# QSTL_MicroDSUB_FFC.net
KiCad netlist of a schematic drawn in Altium Designer
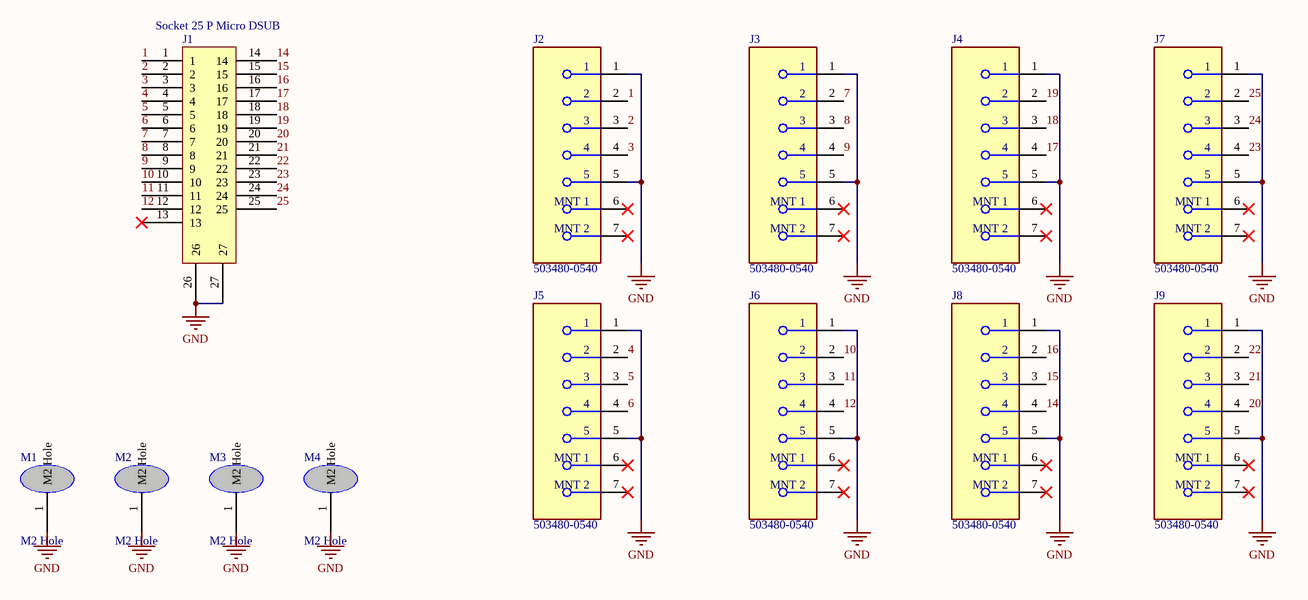
[diagram p0: QSTL_MicroDSUB_FFC.SchDoc]

(export (version "E")
  (design (tool "Eeschema 10.0.6"))
  (components
    (comp (ref "J1")
      (value "Socket 25 P Micro DSUB")
      (footprint "581-M25-213L461")
      (libsource (lib "QSTL_MicroDSUB_FFC") (part "581-M25-213L461"))
    )
    (comp (ref "J2")
      (value "503480-0540")
      (footprint "FP-503480-0540-MFG")
      (description "503480-0540 Connector FFC/FPC SKT 5 Position 0.5mm Solder Right Angle Surface Mount T/R")
      (libsource (lib "Altium Content Vault") (part "6b037d2877ced340e1c65ac82253790"))
    )
    (comp (ref "J3")
      (value "503480-0540")
      (footprint "FP-503480-0540-MFG")
      (description "503480-0540 Connector FFC/FPC SKT 5 Position 0.5mm Solder Right Angle Surface Mount T/R")
      (libsource (lib "Altium Content Vault") (part "6b037d2877ced340e1c65ac82253790"))
    )
    (comp (ref "J4")
      (value "503480-0540")
      (footprint "FP-503480-0540-MFG")
      (description "503480-0540 Connector FFC/FPC SKT 5 Position 0.5mm Solder Right Angle Surface Mount T/R")
      (libsource (lib "Altium Content Vault") (part "6b037d2877ced340e1c65ac82253790"))
    )
    (comp (ref "J5")
      (value "503480-0540")
      (footprint "FP-503480-0540-MFG")
      (description "503480-0540 Connector FFC/FPC SKT 5 Position 0.5mm Solder Right Angle Surface Mount T/R")
      (libsource (lib "Altium Content Vault") (part "6b037d2877ced340e1c65ac82253790"))
    )
    (comp (ref "J6")
      (value "503480-0540")
      (footprint "FP-503480-0540-MFG")
      (description "503480-0540 Connector FFC/FPC SKT 5 Position 0.5mm Solder Right Angle Surface Mount T/R")
      (libsource (lib "Altium Content Vault") (part "6b037d2877ced340e1c65ac82253790"))
    )
    (comp (ref "J7")
      (value "503480-0540")
      (footprint "FP-503480-0540-MFG")
      (description "503480-0540 Connector FFC/FPC SKT 5 Position 0.5mm Solder Right Angle Surface Mount T/R")
      (libsource (lib "Altium Content Vault") (part "6b037d2877ced340e1c65ac82253790"))
    )
    (comp (ref "J8")
      (value "503480-0540")
      (footprint "FP-503480-0540-MFG")
      (description "503480-0540 Connector FFC/FPC SKT 5 Position 0.5mm Solder Right Angle Surface Mount T/R")
      (libsource (lib "Altium Content Vault") (part "6b037d2877ced340e1c65ac82253790"))
    )
    (comp (ref "J9")
      (value "503480-0540")
      (footprint "FP-503480-0540-MFG")
      (description "503480-0540 Connector FFC/FPC SKT 5 Position 0.5mm Solder Right Angle Surface Mount T/R")
      (libsource (lib "Altium Content Vault") (part "6b037d2877ced340e1c65ac82253790"))
    )
    (comp (ref "M1")
      (value "M2 Hole")
      (footprint "M2_Hole")
      (libsource (lib "QSTL_MicroDSUB_FFC") (part "M2_HOLE"))
    )
    (comp (ref "M2")
      (value "M2 Hole")
      (footprint "M2_Hole")
      (libsource (lib "QSTL_MicroDSUB_FFC") (part "M2_HOLE"))
    )
    (comp (ref "M3")
      (value "M2 Hole")
      (footprint "M2_Hole")
      (libsource (lib "QSTL_MicroDSUB_FFC") (part "M2_HOLE"))
    )
    (comp (ref "M4")
      (value "M2 Hole")
      (footprint "M2_Hole")
      (libsource (lib "QSTL_MicroDSUB_FFC") (part "M2_HOLE"))
    )
  )
  (nets
    (net (code "1") (name "/1") (class "Default")
      (node (ref "J1") (pin "1") (pinfunction "1_1") (pintype "passive"))
      (node (ref "J2") (pin "2") (pinfunction "2_2") (pintype "passive"))
    )
    (net (code "2") (name "/2") (class "Default")
      (node (ref "J1") (pin "2") (pinfunction "2_2") (pintype "passive"))
      (node (ref "J2") (pin "3") (pinfunction "3_3") (pintype "passive"))
    )
    (net (code "3") (name "/3") (class "Default")
      (node (ref "J1") (pin "3") (pinfunction "3_3") (pintype "passive"))
      (node (ref "J2") (pin "4") (pinfunction "4_4") (pintype "passive"))
    )
    (net (code "4") (name "/4") (class "Default")
      (node (ref "J1") (pin "4") (pinfunction "4_4") (pintype "passive"))
      (node (ref "J5") (pin "2") (pinfunction "2_2") (pintype "passive"))
    )
    (net (code "5") (name "/5") (class "Default")
      (node (ref "J1") (pin "5") (pinfunction "5_5") (pintype "passive"))
      (node (ref "J5") (pin "3") (pinfunction "3_3") (pintype "passive"))
    )
    (net (code "6") (name "/6") (class "Default")
      (node (ref "J1") (pin "6") (pinfunction "6_6") (pintype "passive"))
      (node (ref "J5") (pin "4") (pinfunction "4_4") (pintype "passive"))
    )
    (net (code "7") (name "/7") (class "Default")
      (node (ref "J1") (pin "7") (pinfunction "7_7") (pintype "passive"))
      (node (ref "J3") (pin "2") (pinfunction "2_2") (pintype "passive"))
    )
    (net (code "8") (name "/8") (class "Default")
      (node (ref "J1") (pin "8") (pinfunction "8_8") (pintype "passive"))
      (node (ref "J3") (pin "3") (pinfunction "3_3") (pintype "passive"))
    )
    (net (code "9") (name "/9") (class "Default")
      (node (ref "J1") (pin "9") (pinfunction "9_9") (pintype "passive"))
      (node (ref "J3") (pin "4") (pinfunction "4_4") (pintype "passive"))
    )
    (net (code "10") (name "/10") (class "Default")
      (node (ref "J1") (pin "10") (pinfunction "10_10") (pintype "passive"))
      (node (ref "J6") (pin "2") (pinfunction "2_2") (pintype "passive"))
    )
    (net (code "11") (name "/11") (class "Default")
      (node (ref "J1") (pin "11") (pinfunction "11_11") (pintype "passive"))
      (node (ref "J6") (pin "3") (pinfunction "3_3") (pintype "passive"))
    )
    (net (code "12") (name "/12") (class "Default")
      (node (ref "J1") (pin "12") (pinfunction "12_12") (pintype "passive"))
      (node (ref "J6") (pin "4") (pinfunction "4_4") (pintype "passive"))
    )
    (net (code "13") (name "/14") (class "Default")
      (node (ref "J1") (pin "14") (pinfunction "14_14") (pintype "passive"))
      (node (ref "J8") (pin "4") (pinfunction "4_4") (pintype "passive"))
    )
    (net (code "14") (name "/15") (class "Default")
      (node (ref "J1") (pin "15") (pinfunction "15_15") (pintype "passive"))
      (node (ref "J8") (pin "3") (pinfunction "3_3") (pintype "passive"))
    )
    (net (code "15") (name "/16") (class "Default")
      (node (ref "J1") (pin "16") (pinfunction "16_16") (pintype "passive"))
      (node (ref "J8") (pin "2") (pinfunction "2_2") (pintype "passive"))
    )
    (net (code "16") (name "/17") (class "Default")
      (node (ref "J1") (pin "17") (pinfunction "17_17") (pintype "passive"))
      (node (ref "J4") (pin "4") (pinfunction "4_4") (pintype "passive"))
    )
    (net (code "17") (name "/18") (class "Default")
      (node (ref "J1") (pin "18") (pinfunction "18_18") (pintype "passive"))
      (node (ref "J4") (pin "3") (pinfunction "3_3") (pintype "passive"))
    )
    (net (code "18") (name "/19") (class "Default")
      (node (ref "J1") (pin "19") (pinfunction "19_19") (pintype "passive"))
      (node (ref "J4") (pin "2") (pinfunction "2_2") (pintype "passive"))
    )
    (net (code "19") (name "/20") (class "Default")
      (node (ref "J1") (pin "20") (pinfunction "20_20") (pintype "passive"))
      (node (ref "J9") (pin "4") (pinfunction "4_4") (pintype "passive"))
    )
    (net (code "20") (name "/21") (class "Default")
      (node (ref "J1") (pin "21") (pinfunction "21_21") (pintype "passive"))
      (node (ref "J9") (pin "3") (pinfunction "3_3") (pintype "passive"))
    )
    (net (code "21") (name "/22") (class "Default")
      (node (ref "J1") (pin "22") (pinfunction "22_22") (pintype "passive"))
      (node (ref "J9") (pin "2") (pinfunction "2_2") (pintype "passive"))
    )
    (net (code "22") (name "/23") (class "Default")
      (node (ref "J1") (pin "23") (pinfunction "23_23") (pintype "passive"))
      (node (ref "J7") (pin "4") (pinfunction "4_4") (pintype "passive"))
    )
    (net (code "23") (name "/24") (class "Default")
      (node (ref "J1") (pin "24") (pinfunction "24_24") (pintype "passive"))
      (node (ref "J7") (pin "3") (pinfunction "3_3") (pintype "passive"))
    )
    (net (code "24") (name "/25") (class "Default")
      (node (ref "J1") (pin "25") (pinfunction "25_25") (pintype "passive"))
      (node (ref "J7") (pin "2") (pinfunction "2_2") (pintype "passive"))
    )
    (net (code "25") (name "GND") (class "Default")
      (node (ref "J1") (pin "26") (pinfunction "26_26") (pintype "passive"))
      (node (ref "J1") (pin "27") (pinfunction "27_27") (pintype "passive"))
      (node (ref "J2") (pin "1") (pinfunction "1_1") (pintype "passive"))
      (node (ref "J2") (pin "5") (pinfunction "5_5") (pintype "passive"))
      (node (ref "J3") (pin "1") (pinfunction "1_1") (pintype "passive"))
      (node (ref "J3") (pin "5") (pinfunction "5_5") (pintype "passive"))
      (node (ref "J4") (pin "1") (pinfunction "1_1") (pintype "passive"))
      (node (ref "J4") (pin "5") (pinfunction "5_5") (pintype "passive"))
      (node (ref "J5") (pin "1") (pinfunction "1_1") (pintype "passive"))
      (node (ref "J5") (pin "5") (pinfunction "5_5") (pintype "passive"))
      (node (ref "J6") (pin "1") (pinfunction "1_1") (pintype "passive"))
      (node (ref "J6") (pin "5") (pinfunction "5_5") (pintype "passive"))
      (node (ref "J7") (pin "1") (pinfunction "1_1") (pintype "passive"))
      (node (ref "J7") (pin "5") (pinfunction "5_5") (pintype "passive"))
      (node (ref "J8") (pin "1") (pinfunction "1_1") (pintype "passive"))
      (node (ref "J8") (pin "5") (pinfunction "5_5") (pintype "passive"))
      (node (ref "J9") (pin "1") (pinfunction "1_1") (pintype "passive"))
      (node (ref "J9") (pin "5") (pinfunction "5_5") (pintype "passive"))
      (node (ref "M1") (pin "1") (pinfunction "M2_Hole_1") (pintype "passive"))
      (node (ref "M2") (pin "1") (pinfunction "M2_Hole_1") (pintype "passive"))
      (node (ref "M3") (pin "1") (pinfunction "M2_Hole_1") (pintype "passive"))
      (node (ref "M4") (pin "1") (pinfunction "M2_Hole_1") (pintype "passive"))
    )
    (net (code "26") (name "unconnected-(J1-Pad13)") (class "Default")
      (node (ref "J1") (pin "13") (pinfunction "13_13") (pintype "passive+no_connect"))
    )
    (net (code "27") (name "unconnected-(J2-MNT_1-Pad6)") (class "Default")
      (node (ref "J2") (pin "6") (pinfunction "MNT_1_6") (pintype "passive+no_connect"))
    )
    (net (code "28") (name "unconnected-(J2-MNT_2-Pad7)") (class "Default")
      (node (ref "J2") (pin "7") (pinfunction "MNT_2_7") (pintype "passive+no_connect"))
    )
    (net (code "29") (name "unconnected-(J3-MNT_1-Pad6)") (class "Default")
      (node (ref "J3") (pin "6") (pinfunction "MNT_1_6") (pintype "passive+no_connect"))
    )
    (net (code "30") (name "unconnected-(J3-MNT_2-Pad7)") (class "Default")
      (node (ref "J3") (pin "7") (pinfunction "MNT_2_7") (pintype "passive+no_connect"))
    )
    (net (code "31") (name "unconnected-(J4-MNT_1-Pad6)") (class "Default")
      (node (ref "J4") (pin "6") (pinfunction "MNT_1_6") (pintype "passive+no_connect"))
    )
    (net (code "32") (name "unconnected-(J4-MNT_2-Pad7)") (class "Default")
      (node (ref "J4") (pin "7") (pinfunction "MNT_2_7") (pintype "passive+no_connect"))
    )
    (net (code "33") (name "unconnected-(J5-MNT_1-Pad6)") (class "Default")
      (node (ref "J5") (pin "6") (pinfunction "MNT_1_6") (pintype "passive+no_connect"))
    )
    (net (code "34") (name "unconnected-(J5-MNT_2-Pad7)") (class "Default")
      (node (ref "J5") (pin "7") (pinfunction "MNT_2_7") (pintype "passive+no_connect"))
    )
    (net (code "35") (name "unconnected-(J6-MNT_1-Pad6)") (class "Default")
      (node (ref "J6") (pin "6") (pinfunction "MNT_1_6") (pintype "passive+no_connect"))
    )
    (net (code "36") (name "unconnected-(J6-MNT_2-Pad7)") (class "Default")
      (node (ref "J6") (pin "7") (pinfunction "MNT_2_7") (pintype "passive+no_connect"))
    )
    (net (code "37") (name "unconnected-(J7-MNT_1-Pad6)") (class "Default")
      (node (ref "J7") (pin "6") (pinfunction "MNT_1_6") (pintype "passive+no_connect"))
    )
    (net (code "38") (name "unconnected-(J7-MNT_2-Pad7)") (class "Default")
      (node (ref "J7") (pin "7") (pinfunction "MNT_2_7") (pintype "passive+no_connect"))
    )
    (net (code "39") (name "unconnected-(J8-MNT_1-Pad6)") (class "Default")
      (node (ref "J8") (pin "6") (pinfunction "MNT_1_6") (pintype "passive+no_connect"))
    )
    (net (code "40") (name "unconnected-(J8-MNT_2-Pad7)") (class "Default")
      (node (ref "J8") (pin "7") (pinfunction "MNT_2_7") (pintype "passive+no_connect"))
    )
    (net (code "41") (name "unconnected-(J9-MNT_1-Pad6)") (class "Default")
      (node (ref "J9") (pin "6") (pinfunction "MNT_1_6") (pintype "passive+no_connect"))
    )
    (net (code "42") (name "unconnected-(J9-MNT_2-Pad7)") (class "Default")
      (node (ref "J9") (pin "7") (pinfunction "MNT_2_7") (pintype "passive+no_connect"))
    )
  )
)
